# carduino-board.net
KiCad netlist of a schematic drawn in EAGLE
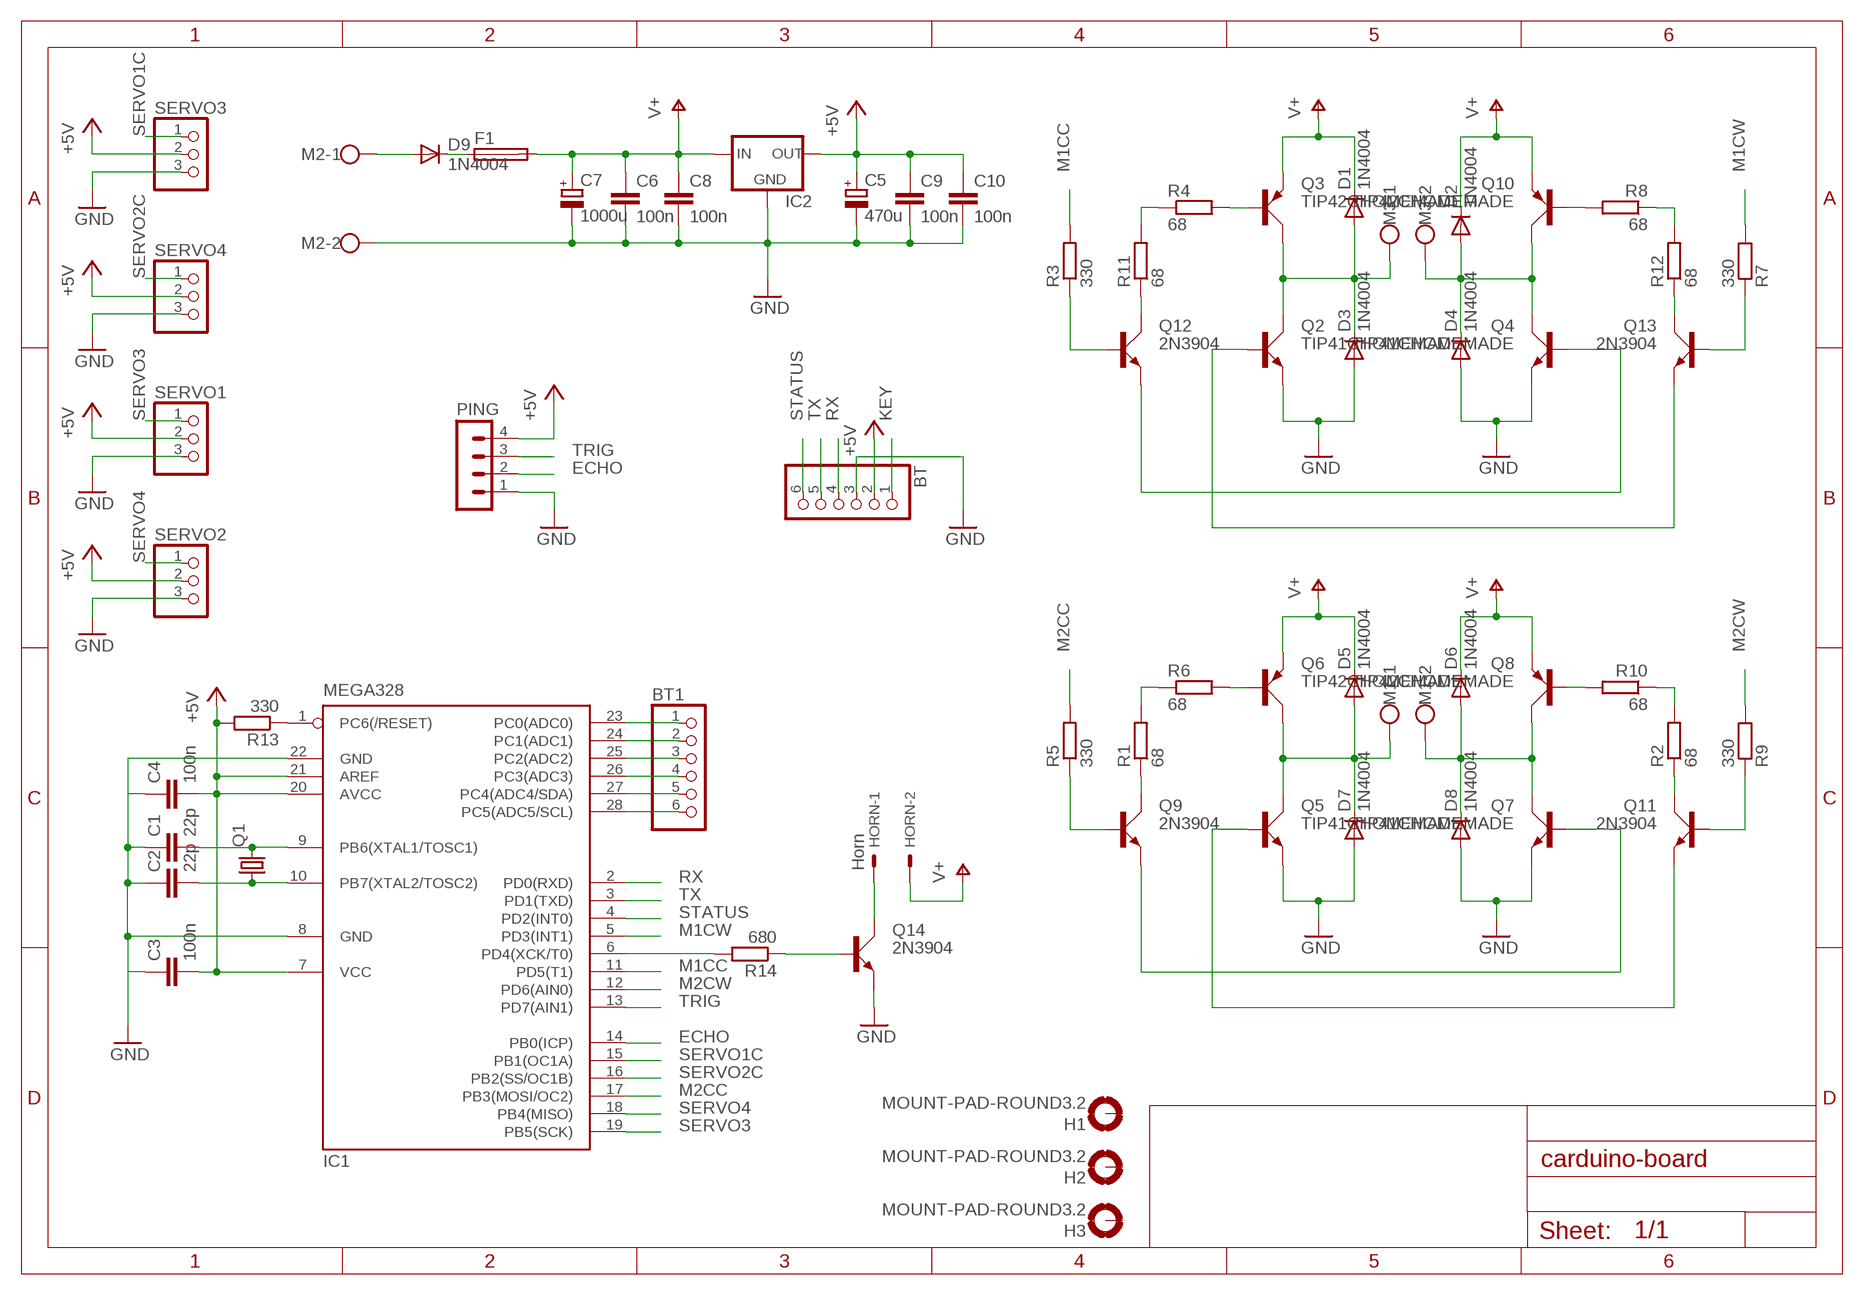
[diagram p0: schematic, sheet 1]

(export (version "E")
  (design (tool "Eeschema 10.0.6"))
  (components
    (comp (ref "BT")
      (value "PINHD-1X6HOMEMADE")
      (footprint "eagle-import:1X06-HOMEMADE")
      (libsource (lib "eagle-import") (part "PINHD-1X6HOMEMADE"))
    )
    (comp (ref "BT1")
      (value "PINHD-1X6HOMEMADE")
      (footprint "eagle-import:1X06-HOMEMADE")
      (libsource (lib "eagle-import") (part "PINHD-1X6HOMEMADE"))
    )
    (comp (ref "C1")
      (value "22p")
      (footprint "eagle-import:C1206K")
      (libsource (lib "eagle-import") (part "C-EUC1206K"))
    )
    (comp (ref "C2")
      (value "22p")
      (footprint "eagle-import:C1206K")
      (libsource (lib "eagle-import") (part "C-EUC1206K"))
    )
    (comp (ref "C3")
      (value "100n")
      (footprint "eagle-import:C1206K")
      (libsource (lib "eagle-import") (part "C-EUC1206K"))
    )
    (comp (ref "C4")
      (value "100n")
      (footprint "eagle-import:C1206K")
      (libsource (lib "eagle-import") (part "C-EUC1206K"))
    )
    (comp (ref "C5")
      (value "470u")
      (footprint "eagle-import:UD-8X10_NICHICON")
      (libsource (lib "eagle-import") (part "CPOL-EUUD-8X10"))
    )
    (comp (ref "C6")
      (value "100n")
      (footprint "eagle-import:C1206K")
      (libsource (lib "eagle-import") (part "C-EUC1206K"))
    )
    (comp (ref "C7")
      (value "1000u")
      (footprint "eagle-import:E3,5-10")
      (libsource (lib "eagle-import") (part "CPOL-EUE3.5-10"))
    )
    (comp (ref "C8")
      (value "100n")
      (footprint "eagle-import:C1206K")
      (libsource (lib "eagle-import") (part "C-EUC1206K"))
    )
    (comp (ref "C9")
      (value "100n")
      (footprint "eagle-import:C1206K")
      (libsource (lib "eagle-import") (part "C-EUC1206K"))
    )
    (comp (ref "C10")
      (value "100n")
      (footprint "eagle-import:C1206K")
      (libsource (lib "eagle-import") (part "C-EUC1206K"))
    )
    (comp (ref "D1")
      (value "1N4004")
      (footprint "eagle-import:DO41-10")
      (libsource (lib "eagle-import") (part "1N4004"))
    )
    (comp (ref "D2")
      (value "1N4004")
      (footprint "eagle-import:DO41-10")
      (libsource (lib "eagle-import") (part "1N4004"))
    )
    (comp (ref "D3")
      (value "1N4004")
      (footprint "eagle-import:DO41-10")
      (libsource (lib "eagle-import") (part "1N4004"))
    )
    (comp (ref "D4")
      (value "1N4004")
      (footprint "eagle-import:DO41-10")
      (libsource (lib "eagle-import") (part "1N4004"))
    )
    (comp (ref "D5")
      (value "1N4004")
      (footprint "eagle-import:DO41-10")
      (libsource (lib "eagle-import") (part "1N4004"))
    )
    (comp (ref "D6")
      (value "1N4004")
      (footprint "eagle-import:DO41-10")
      (libsource (lib "eagle-import") (part "1N4004"))
    )
    (comp (ref "D7")
      (value "1N4004")
      (footprint "eagle-import:DO41-10")
      (libsource (lib "eagle-import") (part "1N4004"))
    )
    (comp (ref "D8")
      (value "1N4004")
      (footprint "eagle-import:DO41-10")
      (libsource (lib "eagle-import") (part "1N4004"))
    )
    (comp (ref "D9")
      (value "1N4004")
      (footprint "eagle-import:DO41-10")
      (libsource (lib "eagle-import") (part "1N4004"))
    )
    (comp (ref "F1")
      (value "TE5")
      (footprint "eagle-import:TE5")
      (libsource (lib "eagle-import") (part "TE5"))
    )
    (comp (ref "H1")
      (value "MOUNT-PAD-ROUND3.2")
      (footprint "eagle-import:3,2-PAD")
      (libsource (lib "eagle-import") (part "MOUNT-PAD-ROUND3.2"))
    )
    (comp (ref "H2")
      (value "MOUNT-PAD-ROUND3.2")
      (footprint "eagle-import:3,2-PAD")
      (libsource (lib "eagle-import") (part "MOUNT-PAD-ROUND3.2"))
    )
    (comp (ref "H3")
      (value "MOUNT-PAD-ROUND3.2")
      (footprint "eagle-import:3,2-PAD")
      (libsource (lib "eagle-import") (part "MOUNT-PAD-ROUND3.2"))
    )
    (comp (ref "HORN")
      (value "Horn")
      (footprint "eagle-import:22-23-2021")
      (fields (field (name "MF") "MOLEX") (field (name "MPN") "22-23-2021"))
      (libsource (lib "eagle-import") (part "22-23-2021"))
    )
    (comp (ref "IC1")
      (value "MEGA328")
      (footprint "eagle-import:DIL28-3")
      (libsource (lib "eagle-import") (part "MEGA8-P"))
    )
    (comp (ref "IC2")
      (value "78XXS")
      (footprint "eagle-import:78XXS")
      (libsource (lib "eagle-import") (part "78XXS"))
    )
    (comp (ref "M1")
      (value "W237-102")
      (footprint "eagle-import:W237-102")
      (fields (field (name "MPN") "237-102"))
      (libsource (lib "eagle-import") (part "W237-102"))
    )
    (comp (ref "M2")
      (value "W237-102")
      (footprint "eagle-import:W237-102")
      (fields (field (name "MPN") "237-102"))
      (libsource (lib "eagle-import") (part "W237-102"))
    )
    (comp (ref "M3")
      (value "W237-102")
      (footprint "eagle-import:W237-102")
      (fields (field (name "MPN") "237-102"))
      (libsource (lib "eagle-import") (part "W237-102"))
    )
    (comp (ref "PING")
      (value "MA04-1HOMEMADE")
      (footprint "eagle-import:MA04-1-HOMEMADE")
      (libsource (lib "eagle-import") (part "MA04-1HOMEMADE"))
    )
    (comp (ref "Q1")
      (value "CRYSTALHC49S")
      (footprint "eagle-import:HC49_S")
      (libsource (lib "eagle-import") (part "CRYSTALHC49S"))
    )
    (comp (ref "Q2")
      (value "TIP41CHOMEMADE")
      (footprint "eagle-import:TO220AV-HOMEMADE")
      (libsource (lib "eagle-import") (part "TIP41CHOMEMADE"))
    )
    (comp (ref "Q3")
      (value "TIP42CHOMEMADE")
      (footprint "eagle-import:TO220AV-HOMEMADE")
      (libsource (lib "eagle-import") (part "TIP42CHOMEMADE"))
    )
    (comp (ref "Q4")
      (value "TIP41CHOMEMADE")
      (footprint "eagle-import:TO220AV-HOMEMADE")
      (libsource (lib "eagle-import") (part "TIP41CHOMEMADE"))
    )
    (comp (ref "Q5")
      (value "TIP41CHOMEMADE")
      (footprint "eagle-import:TO220AV-HOMEMADE")
      (libsource (lib "eagle-import") (part "TIP41CHOMEMADE"))
    )
    (comp (ref "Q6")
      (value "TIP42CHOMEMADE")
      (footprint "eagle-import:TO220AV-HOMEMADE")
      (libsource (lib "eagle-import") (part "TIP42CHOMEMADE"))
    )
    (comp (ref "Q7")
      (value "TIP41CHOMEMADE")
      (footprint "eagle-import:TO220AV-HOMEMADE")
      (libsource (lib "eagle-import") (part "TIP41CHOMEMADE"))
    )
    (comp (ref "Q8")
      (value "TIP42CHOMEMADE")
      (footprint "eagle-import:TO220AV-HOMEMADE")
      (libsource (lib "eagle-import") (part "TIP42CHOMEMADE"))
    )
    (comp (ref "Q9")
      (value "2N3904")
      (footprint "eagle-import:TO92D")
      (libsource (lib "eagle-import") (part "2N3904"))
    )
    (comp (ref "Q10")
      (value "TIP42CHOMEMADE")
      (footprint "eagle-import:TO220AV-HOMEMADE")
      (libsource (lib "eagle-import") (part "TIP42CHOMEMADE"))
    )
    (comp (ref "Q11")
      (value "2N3904")
      (footprint "eagle-import:TO92D")
      (libsource (lib "eagle-import") (part "2N3904"))
    )
    (comp (ref "Q12")
      (value "2N3904")
      (footprint "eagle-import:TO92D")
      (libsource (lib "eagle-import") (part "2N3904"))
    )
    (comp (ref "Q13")
      (value "2N3904")
      (footprint "eagle-import:TO92D")
      (libsource (lib "eagle-import") (part "2N3904"))
    )
    (comp (ref "Q14")
      (value "2N3904")
      (footprint "eagle-import:TO92D")
      (libsource (lib "eagle-import") (part "2N3904"))
    )
    (comp (ref "R1")
      (value "68")
      (footprint "eagle-import:M1206")
      (libsource (lib "eagle-import") (part "R-EU_M1206"))
    )
    (comp (ref "R2")
      (value "68")
      (footprint "eagle-import:M1206")
      (libsource (lib "eagle-import") (part "R-EU_M1206"))
    )
    (comp (ref "R3")
      (value "330")
      (footprint "eagle-import:M1206")
      (libsource (lib "eagle-import") (part "R-EU_M1206"))
    )
    (comp (ref "R4")
      (value "68")
      (footprint "eagle-import:M1206")
      (libsource (lib "eagle-import") (part "R-EU_M1206"))
    )
    (comp (ref "R5")
      (value "330")
      (footprint "eagle-import:M1206")
      (libsource (lib "eagle-import") (part "R-EU_M1206"))
    )
    (comp (ref "R6")
      (value "68")
      (footprint "eagle-import:M1206")
      (libsource (lib "eagle-import") (part "R-EU_M1206"))
    )
    (comp (ref "R7")
      (value "330")
      (footprint "eagle-import:M1206")
      (libsource (lib "eagle-import") (part "R-EU_M1206"))
    )
    (comp (ref "R8")
      (value "68")
      (footprint "eagle-import:M1206")
      (libsource (lib "eagle-import") (part "R-EU_M1206"))
    )
    (comp (ref "R9")
      (value "330")
      (footprint "eagle-import:M1206")
      (libsource (lib "eagle-import") (part "R-EU_M1206"))
    )
    (comp (ref "R10")
      (value "68")
      (footprint "eagle-import:M1206")
      (libsource (lib "eagle-import") (part "R-EU_M1206"))
    )
    (comp (ref "R11")
      (value "68")
      (footprint "eagle-import:M1206")
      (libsource (lib "eagle-import") (part "R-EU_M1206"))
    )
    (comp (ref "R12")
      (value "68")
      (footprint "eagle-import:M1206")
      (libsource (lib "eagle-import") (part "R-EU_M1206"))
    )
    (comp (ref "R13")
      (value "330")
      (footprint "eagle-import:M1206")
      (libsource (lib "eagle-import") (part "R-EU_M1206"))
    )
    (comp (ref "R14")
      (value "680")
      (footprint "eagle-import:M1206")
      (libsource (lib "eagle-import") (part "R-EU_M1206"))
    )
    (comp (ref "SERVO1")
      (value "PINHD-1X3HOMEMADE")
      (footprint "eagle-import:1X03-HOMEMADE")
      (libsource (lib "eagle-import") (part "PINHD-1X3HOMEMADE"))
    )
    (comp (ref "SERVO2")
      (value "PINHD-1X3HOMEMADE")
      (footprint "eagle-import:1X03-HOMEMADE")
      (libsource (lib "eagle-import") (part "PINHD-1X3HOMEMADE"))
    )
    (comp (ref "SERVO3")
      (value "PINHD-1X3HOMEMADE")
      (footprint "eagle-import:1X03-HOMEMADE")
      (libsource (lib "eagle-import") (part "PINHD-1X3HOMEMADE"))
    )
    (comp (ref "SERVO4")
      (value "PINHD-1X3HOMEMADE")
      (footprint "eagle-import:1X03-HOMEMADE")
      (libsource (lib "eagle-import") (part "PINHD-1X3HOMEMADE"))
    )
  )
  (nets
    (net (code "1") (name "+5V") (class "Default")
      (node (ref "BT") (pin "2") (pinfunction "2_2") (pintype "passive"))
      (node (ref "C10") (pin "1") (pinfunction "1_1") (pintype "passive"))
      (node (ref "C3") (pin "2") (pinfunction "2_2") (pintype "passive"))
      (node (ref "C4") (pin "2") (pinfunction "2_2") (pintype "passive"))
      (node (ref "C5") (pin "+") (pinfunction "+_+") (pintype "passive"))
      (node (ref "C9") (pin "1") (pinfunction "1_1") (pintype "passive"))
      (node (ref "IC1") (pin "20") (pinfunction "AVCC_20") (pintype "power_in"))
      (node (ref "IC1") (pin "21") (pinfunction "AREF_21") (pintype "passive"))
      (node (ref "IC1") (pin "7") (pinfunction "VCC_7") (pintype "power_in"))
      (node (ref "IC2") (pin "OUT") (pinfunction "OUT_OUT") (pintype "passive"))
      (node (ref "PING") (pin "4") (pinfunction "4_4") (pintype "passive"))
      (node (ref "R13") (pin "2") (pinfunction "2_2") (pintype "passive"))
      (node (ref "SERVO1") (pin "2") (pinfunction "2_2") (pintype "passive"))
      (node (ref "SERVO2") (pin "2") (pinfunction "2_2") (pintype "passive"))
      (node (ref "SERVO3") (pin "2") (pinfunction "2_2") (pintype "passive"))
      (node (ref "SERVO4") (pin "2") (pinfunction "2_2") (pintype "passive"))
    )
    (net (code "2") (name "/ECHO") (class "Default")
      (node (ref "IC1") (pin "14") (pinfunction "PB0(ICP)_14") (pintype "bidirectional"))
      (node (ref "PING") (pin "2") (pinfunction "2_2") (pintype "passive"))
    )
    (net (code "3") (name "/KEY") (class "Default")
      (node (ref "BT") (pin "1") (pinfunction "1_1") (pintype "passive"))
    )
    (net (code "4") (name "/M1CC") (class "Default")
      (node (ref "IC1") (pin "11") (pinfunction "PD5(T1)_11") (pintype "bidirectional"))
      (node (ref "R3") (pin "2") (pinfunction "2_2") (pintype "passive"))
    )
    (net (code "5") (name "/M1CW") (class "Default")
      (node (ref "IC1") (pin "5") (pinfunction "PD3(INT1)_5") (pintype "bidirectional"))
      (node (ref "R7") (pin "2") (pinfunction "2_2") (pintype "passive"))
    )
    (net (code "6") (name "/M2CC") (class "Default")
      (node (ref "IC1") (pin "17") (pinfunction "PB3(MOSI/OC2)_17") (pintype "bidirectional"))
      (node (ref "R5") (pin "2") (pinfunction "2_2") (pintype "passive"))
    )
    (net (code "7") (name "/M2CW") (class "Default")
      (node (ref "IC1") (pin "12") (pinfunction "PD6(AIN0)_12") (pintype "bidirectional"))
      (node (ref "R9") (pin "2") (pinfunction "2_2") (pintype "passive"))
    )
    (net (code "8") (name "/RX") (class "Default")
      (node (ref "BT") (pin "4") (pinfunction "4_4") (pintype "passive"))
      (node (ref "IC1") (pin "2") (pinfunction "PD0(RXD)_2") (pintype "bidirectional"))
    )
    (net (code "9") (name "/SERVO1C") (class "Default")
      (node (ref "IC1") (pin "15") (pinfunction "PB1(OC1A)_15") (pintype "bidirectional"))
      (node (ref "SERVO3") (pin "1") (pinfunction "1_1") (pintype "passive"))
    )
    (net (code "10") (name "/SERVO2C") (class "Default")
      (node (ref "IC1") (pin "16") (pinfunction "PB2(SS/OC1B)_16") (pintype "bidirectional"))
      (node (ref "SERVO4") (pin "1") (pinfunction "1_1") (pintype "passive"))
    )
    (net (code "11") (name "/SERVO3") (class "Default")
      (node (ref "IC1") (pin "19") (pinfunction "PB5(SCK)_19") (pintype "bidirectional"))
      (node (ref "SERVO1") (pin "1") (pinfunction "1_1") (pintype "passive"))
    )
    (net (code "12") (name "/SERVO4") (class "Default")
      (node (ref "IC1") (pin "18") (pinfunction "PB4(MISO)_18") (pintype "bidirectional"))
      (node (ref "SERVO2") (pin "1") (pinfunction "1_1") (pintype "passive"))
    )
    (net (code "13") (name "/STATUS") (class "Default")
      (node (ref "BT") (pin "6") (pinfunction "6_6") (pintype "passive"))
      (node (ref "IC1") (pin "4") (pinfunction "PD2(INT0)_4") (pintype "bidirectional"))
    )
    (net (code "14") (name "/TRIG") (class "Default")
      (node (ref "IC1") (pin "13") (pinfunction "PD7(AIN1)_13") (pintype "bidirectional"))
      (node (ref "PING") (pin "3") (pinfunction "3_3") (pintype "passive"))
    )
    (net (code "15") (name "/TX") (class "Default")
      (node (ref "BT") (pin "5") (pinfunction "5_5") (pintype "passive"))
      (node (ref "IC1") (pin "3") (pinfunction "PD1(TXD)_3") (pintype "bidirectional"))
    )
    (net (code "16") (name "GND") (class "Default")
      (node (ref "BT") (pin "3") (pinfunction "3_3") (pintype "passive"))
      (node (ref "C1") (pin "1") (pinfunction "1_1") (pintype "passive"))
      (node (ref "C10") (pin "2") (pinfunction "2_2") (pintype "passive"))
      (node (ref "C2") (pin "1") (pinfunction "1_1") (pintype "passive"))
      (node (ref "C3") (pin "1") (pinfunction "1_1") (pintype "passive"))
      (node (ref "C4") (pin "1") (pinfunction "1_1") (pintype "passive"))
      (node (ref "C5") (pin "-") (pinfunction "-_-") (pintype "passive"))
      (node (ref "C6") (pin "2") (pinfunction "2_2") (pintype "passive"))
      (node (ref "C7") (pin "-") (pinfunction "-_-") (pintype "passive"))
      (node (ref "C8") (pin "2") (pinfunction "2_2") (pintype "passive"))
      (node (ref "C9") (pin "2") (pinfunction "2_2") (pintype "passive"))
      (node (ref "D3") (pin "A") (pinfunction "A_A") (pintype "passive"))
      (node (ref "D4") (pin "A") (pinfunction "A_A") (pintype "passive"))
      (node (ref "D7") (pin "A") (pinfunction "A_A") (pintype "passive"))
      (node (ref "D8") (pin "A") (pinfunction "A_A") (pintype "passive"))
      (node (ref "IC1") (pin "22") (pinfunction "GND_22") (pintype "power_in"))
      (node (ref "IC1") (pin "8") (pinfunction "GND_8") (pintype "power_in"))
      (node (ref "IC2") (pin "GND") (pinfunction "GND_GND") (pintype "input"))
      (node (ref "M2") (pin "2") (pinfunction "KL_2") (pintype "passive"))
      (node (ref "PING") (pin "1") (pinfunction "1_1") (pintype "passive"))
      (node (ref "Q14") (pin "E") (pinfunction "E_E") (pintype "passive"))
      (node (ref "Q2") (pin "E") (pinfunction "E_E") (pintype "passive"))
      (node (ref "Q4") (pin "E") (pinfunction "E_E") (pintype "passive"))
      (node (ref "Q5") (pin "E") (pinfunction "E_E") (pintype "passive"))
      (node (ref "Q7") (pin "E") (pinfunction "E_E") (pintype "passive"))
      (node (ref "SERVO1") (pin "3") (pinfunction "3_3") (pintype "passive"))
      (node (ref "SERVO2") (pin "3") (pinfunction "3_3") (pintype "passive"))
      (node (ref "SERVO3") (pin "3") (pinfunction "3_3") (pintype "passive"))
      (node (ref "SERVO4") (pin "3") (pinfunction "3_3") (pintype "passive"))
    )
    (net (code "17") (name "Net-(D9-PadC)") (class "Default")
      (node (ref "D9") (pin "C") (pinfunction "C_C") (pintype "passive"))
      (node (ref "F1") (pin "1") (pinfunction "1_1") (pintype "passive"))
    )
    (net (code "18") (name "Net-(HORNA-S)") (class "Default")
      (node (ref "HORN") (pin "1") (pinfunction "S_1") (pintype "passive"))
      (node (ref "Q14") (pin "C") (pinfunction "C_C") (pintype "passive"))
    )
    (net (code "19") (name "Net-(IC1-PB6(XTAL1{slash}TOSC1))") (class "Default")
      (node (ref "C1") (pin "2") (pinfunction "2_2") (pintype "passive"))
      (node (ref "IC1") (pin "9") (pinfunction "PB6(XTAL1/TOSC1)_9") (pintype "bidirectional"))
      (node (ref "Q1") (pin "2") (pinfunction "2_2") (pintype "passive"))
    )
    (net (code "20") (name "Net-(IC1-PB7(XTAL2{slash}TOSC2))") (class "Default")
      (node (ref "C2") (pin "2") (pinfunction "2_2") (pintype "passive"))
      (node (ref "IC1") (pin "10") (pinfunction "PB7(XTAL2/TOSC2)_10") (pintype "bidirectional"))
      (node (ref "Q1") (pin "1") (pinfunction "1_1") (pintype "passive"))
    )
    (net (code "21") (name "Net-(IC1-PC0(ADC0))") (class "Default")
      (node (ref "BT1") (pin "1") (pinfunction "1_1") (pintype "passive"))
      (node (ref "IC1") (pin "23") (pinfunction "PC0(ADC0)_23") (pintype "bidirectional"))
    )
    (net (code "22") (name "Net-(IC1-PC1(ADC1))") (class "Default")
      (node (ref "BT1") (pin "2") (pinfunction "2_2") (pintype "passive"))
      (node (ref "IC1") (pin "24") (pinfunction "PC1(ADC1)_24") (pintype "bidirectional"))
    )
    (net (code "23") (name "Net-(IC1-PC2(ADC2))") (class "Default")
      (node (ref "BT1") (pin "3") (pinfunction "3_3") (pintype "passive"))
      (node (ref "IC1") (pin "25") (pinfunction "PC2(ADC2)_25") (pintype "bidirectional"))
    )
    (net (code "24") (name "Net-(IC1-PC3(ADC3))") (class "Default")
      (node (ref "BT1") (pin "4") (pinfunction "4_4") (pintype "passive"))
      (node (ref "IC1") (pin "26") (pinfunction "PC3(ADC3)_26") (pintype "bidirectional"))
    )
    (net (code "25") (name "Net-(IC1-PC4(ADC4{slash}SDA))") (class "Default")
      (node (ref "BT1") (pin "5") (pinfunction "5_5") (pintype "passive"))
      (node (ref "IC1") (pin "27") (pinfunction "PC4(ADC4/SDA)_27") (pintype "bidirectional"))
    )
    (net (code "26") (name "Net-(IC1-PC5(ADC5{slash}SCL))") (class "Default")
      (node (ref "BT1") (pin "6") (pinfunction "6_6") (pintype "passive"))
      (node (ref "IC1") (pin "28") (pinfunction "PC5(ADC5/SCL)_28") (pintype "bidirectional"))
    )
    (net (code "27") (name "Net-(IC1-PC6({slash}RESET))") (class "Default")
      (node (ref "IC1") (pin "1") (pinfunction "PC6(/RESET)_1") (pintype "bidirectional"))
      (node (ref "R13") (pin "1") (pinfunction "1_1") (pintype "passive"))
    )
    (net (code "28") (name "Net-(IC1-PD4(XCK{slash}T0))") (class "Default")
      (node (ref "IC1") (pin "6") (pinfunction "PD4(XCK/T0)_6") (pintype "bidirectional"))
      (node (ref "R14") (pin "2") (pinfunction "2_2") (pintype "passive"))
    )
    (net (code "29") (name "Net-(M1A-KL)") (class "Default")
      (node (ref "D5") (pin "A") (pinfunction "A_A") (pintype "passive"))
      (node (ref "D7") (pin "C") (pinfunction "C_C") (pintype "passive"))
      (node (ref "M1") (pin "1") (pinfunction "KL_1") (pintype "passive"))
      (node (ref "Q5") (pin "C") (pinfunction "C_C") (pintype "passive"))
      (node (ref "Q6") (pin "C") (pinfunction "C_C") (pintype "passive"))
    )
    (net (code "30") (name "Net-(M1B-KL)") (class "Default")
      (node (ref "D6") (pin "A") (pinfunction "A_A") (pintype "passive"))
      (node (ref "D8") (pin "C") (pinfunction "C_C") (pintype "passive"))
      (node (ref "M1") (pin "2") (pinfunction "KL_2") (pintype "passive"))
      (node (ref "Q7") (pin "C") (pinfunction "C_C") (pintype "passive"))
      (node (ref "Q8") (pin "C") (pinfunction "C_C") (pintype "passive"))
    )
    (net (code "31") (name "Net-(M2A-KL)") (class "Default")
      (node (ref "D9") (pin "A") (pinfunction "A_A") (pintype "passive"))
      (node (ref "M2") (pin "1") (pinfunction "KL_1") (pintype "passive"))
    )
    (net (code "32") (name "Net-(M3A-KL)") (class "Default")
      (node (ref "D1") (pin "A") (pinfunction "A_A") (pintype "passive"))
      (node (ref "D3") (pin "C") (pinfunction "C_C") (pintype "passive"))
      (node (ref "M3") (pin "1") (pinfunction "KL_1") (pintype "passive"))
      (node (ref "Q2") (pin "C") (pinfunction "C_C") (pintype "passive"))
      (node (ref "Q3") (pin "C") (pinfunction "C_C") (pintype "passive"))
    )
    (net (code "33") (name "Net-(M3B-KL)") (class "Default")
      (node (ref "D2") (pin "A") (pinfunction "A_A") (pintype "passive"))
      (node (ref "D4") (pin "C") (pinfunction "C_C") (pintype "passive"))
      (node (ref "M3") (pin "2") (pinfunction "KL_2") (pintype "passive"))
      (node (ref "Q10") (pin "C") (pinfunction "C_C") (pintype "passive"))
      (node (ref "Q4") (pin "C") (pinfunction "C_C") (pintype "passive"))
    )
    (net (code "34") (name "Net-(Q3-PadB)") (class "Default")
      (node (ref "Q3") (pin "B") (pinfunction "B_B") (pintype "passive"))
      (node (ref "R4") (pin "2") (pinfunction "2_2") (pintype "passive"))
    )
    (net (code "35") (name "Net-(Q6-PadB)") (class "Default")
      (node (ref "Q6") (pin "B") (pinfunction "B_B") (pintype "passive"))
      (node (ref "R6") (pin "2") (pinfunction "2_2") (pintype "passive"))
    )
    (net (code "36") (name "Net-(Q7-PadB)") (class "Default")
      (node (ref "Q7") (pin "B") (pinfunction "B_B") (pintype "passive"))
      (node (ref "Q9") (pin "E") (pinfunction "E_E") (pintype "passive"))
    )
    (net (code "37") (name "Net-(Q8-PadB)") (class "Default")
      (node (ref "Q8") (pin "B") (pinfunction "B_B") (pintype "passive"))
      (node (ref "R10") (pin "2") (pinfunction "2_2") (pintype "passive"))
    )
    (net (code "38") (name "Net-(Q9-PadB)") (class "Default")
      (node (ref "Q9") (pin "B") (pinfunction "B_B") (pintype "passive"))
      (node (ref "R5") (pin "1") (pinfunction "1_1") (pintype "passive"))
    )
    (net (code "39") (name "Net-(Q9-PadC)") (class "Default")
      (node (ref "Q9") (pin "C") (pinfunction "C_C") (pintype "passive"))
      (node (ref "R1") (pin "1") (pinfunction "1_1") (pintype "passive"))
    )
    (net (code "40") (name "Net-(Q10-PadB)") (class "Default")
      (node (ref "Q10") (pin "B") (pinfunction "B_B") (pintype "passive"))
      (node (ref "R8") (pin "2") (pinfunction "2_2") (pintype "passive"))
    )
    (net (code "41") (name "Net-(Q11-PadB)") (class "Default")
      (node (ref "Q11") (pin "B") (pinfunction "B_B") (pintype "passive"))
      (node (ref "R9") (pin "1") (pinfunction "1_1") (pintype "passive"))
    )
    (net (code "42") (name "Net-(Q11-PadC)") (class "Default")
      (node (ref "Q11") (pin "C") (pinfunction "C_C") (pintype "passive"))
      (node (ref "R2") (pin "1") (pinfunction "1_1") (pintype "passive"))
    )
    (net (code "43") (name "Net-(Q11-PadE)") (class "Default")
      (node (ref "Q11") (pin "E") (pinfunction "E_E") (pintype "passive"))
      (node (ref "Q5") (pin "B") (pinfunction "B_B") (pintype "passive"))
    )
    (net (code "44") (name "Net-(Q12-PadB)") (class "Default")
      (node (ref "Q12") (pin "B") (pinfunction "B_B") (pintype "passive"))
      (node (ref "R3") (pin "1") (pinfunction "1_1") (pintype "passive"))
    )
    (net (code "45") (name "Net-(Q12-PadC)") (class "Default")
      (node (ref "Q12") (pin "C") (pinfunction "C_C") (pintype "passive"))
      (node (ref "R11") (pin "1") (pinfunction "1_1") (pintype "passive"))
    )
    (net (code "46") (name "Net-(Q12-PadE)") (class "Default")
      (node (ref "Q12") (pin "E") (pinfunction "E_E") (pintype "passive"))
      (node (ref "Q4") (pin "B") (pinfunction "B_B") (pintype "passive"))
    )
    (net (code "47") (name "Net-(Q13-PadB)") (class "Default")
      (node (ref "Q13") (pin "B") (pinfunction "B_B") (pintype "passive"))
      (node (ref "R7") (pin "1") (pinfunction "1_1") (pintype "passive"))
    )
    (net (code "48") (name "Net-(Q13-PadC)") (class "Default")
      (node (ref "Q13") (pin "C") (pinfunction "C_C") (pintype "passive"))
      (node (ref "R12") (pin "1") (pinfunction "1_1") (pintype "passive"))
    )
    (net (code "49") (name "Net-(Q13-PadE)") (class "Default")
      (node (ref "Q13") (pin "E") (pinfunction "E_E") (pintype "passive"))
      (node (ref "Q2") (pin "B") (pinfunction "B_B") (pintype "passive"))
    )
    (net (code "50") (name "Net-(Q14-PadB)") (class "Default")
      (node (ref "Q14") (pin "B") (pinfunction "B_B") (pintype "passive"))
      (node (ref "R14") (pin "1") (pinfunction "1_1") (pintype "passive"))
    )
    (net (code "51") (name "Net-(R1-Pad2)") (class "Default")
      (node (ref "R1") (pin "2") (pinfunction "2_2") (pintype "passive"))
      (node (ref "R6") (pin "1") (pinfunction "1_1") (pintype "passive"))
    )
    (net (code "52") (name "Net-(R10-Pad1)") (class "Default")
      (node (ref "R10") (pin "1") (pinfunction "1_1") (pintype "passive"))
      (node (ref "R2") (pin "2") (pinfunction "2_2") (pintype "passive"))
    )
    (net (code "53") (name "Net-(R11-Pad2)") (class "Default")
      (node (ref "R11") (pin "2") (pinfunction "2_2") (pintype "passive"))
      (node (ref "R4") (pin "1") (pinfunction "1_1") (pintype "passive"))
    )
    (net (code "54") (name "Net-(R12-Pad2)") (class "Default")
      (node (ref "R12") (pin "2") (pinfunction "2_2") (pintype "passive"))
      (node (ref "R8") (pin "1") (pinfunction "1_1") (pintype "passive"))
    )
    (net (code "55") (name "V+") (class "Default")
      (node (ref "C6") (pin "1") (pinfunction "1_1") (pintype "passive"))
      (node (ref "C7") (pin "+") (pinfunction "+_+") (pintype "passive"))
      (node (ref "C8") (pin "1") (pinfunction "1_1") (pintype "passive"))
      (node (ref "D1") (pin "C") (pinfunction "C_C") (pintype "passive"))
      (node (ref "D2") (pin "C") (pinfunction "C_C") (pintype "passive"))
      (node (ref "D5") (pin "C") (pinfunction "C_C") (pintype "passive"))
      (node (ref "D6") (pin "C") (pinfunction "C_C") (pintype "passive"))
      (node (ref "F1") (pin "2") (pinfunction "2_2") (pintype "passive"))
      (node (ref "HORN") (pin "2") (pinfunction "S_2") (pintype "passive"))
      (node (ref "IC2") (pin "IN") (pinfunction "IN_IN") (pintype "input"))
      (node (ref "Q10") (pin "E") (pinfunction "E_E") (pintype "passive"))
      (node (ref "Q3") (pin "E") (pinfunction "E_E") (pintype "passive"))
      (node (ref "Q6") (pin "E") (pinfunction "E_E") (pintype "passive"))
      (node (ref "Q8") (pin "E") (pinfunction "E_E") (pintype "passive"))
    )
    (net (code "56") (name "unconnected-(H1-MOUNT-PadB3,2)") (class "Default")
      (node (ref "H1") (pin "B3,2") (pinfunction "MOUNT_B3,2") (pintype "passive"))
    )
    (net (code "57") (name "unconnected-(H2-MOUNT-PadB3,2)") (class "Default")
      (node (ref "H2") (pin "B3,2") (pinfunction "MOUNT_B3,2") (pintype "passive"))
    )
    (net (code "58") (name "unconnected-(H3-MOUNT-PadB3,2)") (class "Default")
      (node (ref "H3") (pin "B3,2") (pinfunction "MOUNT_B3,2") (pintype "passive"))
    )
  )
)
